# obc_imu.net
KiCad netlist of a schematic drawn in Altium Designer
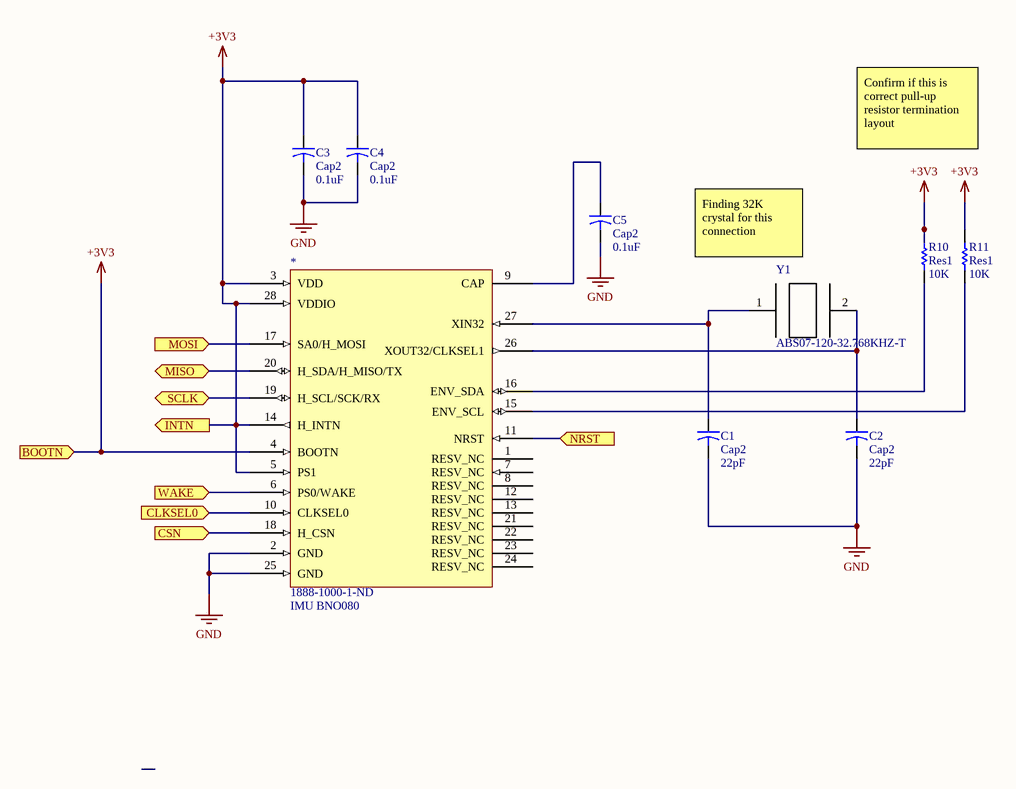
[diagram p0: obc_imu.SchDoc]

(export (version "E")
  (design (tool "Eeschema 10.0.6"))
  (components
    (comp (ref "*")
      (value "IMU BNO080")
      (description "ACCEL/GYRO/MAG I2C 32BIT")
      (libsource (lib "ICs") (part "IMU BNO080"))
    )
    (comp (ref "C1")
      (value "Cap2")
      (footprint "CAPR5-4X5")
      (description "Capacitor")
      (fields (field (name "ALTIUM_VALUE") "22pF") (field (name "PUBLISHER") "Altium Limited"))
      (libsource (lib "Miscellaneous Devices") (part "Cap2"))
    )
    (comp (ref "C2")
      (value "Cap2")
      (footprint "CAPR5-4X5")
      (description "Capacitor")
      (fields (field (name "ALTIUM_VALUE") "22pF") (field (name "PUBLISHER") "Altium Limited"))
      (libsource (lib "Miscellaneous Devices") (part "Cap2"))
    )
    (comp (ref "C3")
      (value "Cap2")
      (footprint "CAPR5-4X5")
      (description "Capacitor")
      (fields (field (name "ALTIUM_VALUE") "0.1uF") (field (name "PUBLISHER") "Altium Limited"))
      (libsource (lib "Miscellaneous Devices") (part "Cap2"))
    )
    (comp (ref "C4")
      (value "Cap2")
      (footprint "CAPR5-4X5")
      (description "Capacitor")
      (fields (field (name "ALTIUM_VALUE") "0.1uF") (field (name "PUBLISHER") "Altium Limited"))
      (libsource (lib "Miscellaneous Devices") (part "Cap2"))
    )
    (comp (ref "C5")
      (value "Cap2")
      (footprint "CAPR5-4X5")
      (description "Capacitor")
      (fields (field (name "ALTIUM_VALUE") "0.1uF") (field (name "PUBLISHER") "Altium Limited"))
      (libsource (lib "Miscellaneous Devices") (part "Cap2"))
    )
    (comp (ref "R10")
      (value "Res1")
      (footprint "AXIAL-0.3")
      (description "Resistor")
      (fields (field (name "ALTIUM_VALUE") "10K") (field (name "PUBLISHER") "Altium Limited"))
      (libsource (lib "Miscellaneous Devices") (part "Res1"))
    )
    (comp (ref "R11")
      (value "Res1")
      (footprint "AXIAL-0.3")
      (description "Resistor")
      (fields (field (name "ALTIUM_VALUE") "10K") (field (name "PUBLISHER") "Altium Limited"))
      (libsource (lib "Miscellaneous Devices") (part "Res1"))
    )
    (comp (ref "Y1")
      (value "ABS07-120-32.768KHZ-T")
      (footprint "XTAL_ABS07-120-32.768KHZ-T")
      (fields (field (name "MF") "Abracon"))
      (libsource (lib "ABS07-120-32.768KHZ-T") (part "ABS07-120-32.768KHZ-T"))
    )
  )
  (nets
    (net (code "1") (name "+3V3") (class "Default")
      (node (ref "*") (pin "14") (pinfunction "H_INTN_14") (pintype "output"))
      (node (ref "*") (pin "28") (pinfunction "VDDIO_28") (pintype "input"))
      (node (ref "*") (pin "3") (pinfunction "VDD_3") (pintype "input"))
      (node (ref "*") (pin "4") (pinfunction "BOOTN_4") (pintype "input"))
      (node (ref "*") (pin "5") (pinfunction "PS1_5") (pintype "input"))
      (node (ref "C3") (pin "1") (pinfunction "1_1") (pintype "passive"))
      (node (ref "C4") (pin "1") (pinfunction "1_1") (pintype "passive"))
      (node (ref "R10") (pin "2") (pinfunction "2_2") (pintype "passive"))
      (node (ref "R11") (pin "2") (pinfunction "2_2") (pintype "passive"))
    )
    (net (code "2") (name "/CLKSEL0") (class "Default")
      (node (ref "*") (pin "10") (pinfunction "CLKSEL0_10") (pintype "input"))
    )
    (net (code "3") (name "/CSN") (class "Default")
      (node (ref "*") (pin "18") (pinfunction "H_CSN_18") (pintype "input"))
    )
    (net (code "4") (name "/MISO") (class "Default")
      (node (ref "*") (pin "20") (pinfunction "H_SDA/H_MISO/TX_20") (pintype "bidirectional"))
    )
    (net (code "5") (name "/MOSI") (class "Default")
      (node (ref "*") (pin "17") (pinfunction "SA0/H_MOSI_17") (pintype "input"))
    )
    (net (code "6") (name "/NRST") (class "Default")
      (node (ref "*") (pin "11") (pinfunction "NRST_11") (pintype "input"))
    )
    (net (code "7") (name "/SCLK") (class "Default")
      (node (ref "*") (pin "19") (pinfunction "H_SCL/SCK/RX_19") (pintype "bidirectional"))
    )
    (net (code "8") (name "/WAKE") (class "Default")
      (node (ref "*") (pin "6") (pinfunction "PS0/WAKE_6") (pintype "input"))
    )
    (net (code "9") (name "GND") (class "Default")
      (node (ref "*") (pin "2") (pinfunction "GND_2") (pintype "input"))
      (node (ref "*") (pin "25") (pinfunction "GND_25") (pintype "input"))
      (node (ref "C1") (pin "2") (pinfunction "2_2") (pintype "passive"))
      (node (ref "C2") (pin "2") (pinfunction "2_2") (pintype "passive"))
      (node (ref "C3") (pin "2") (pinfunction "2_2") (pintype "passive"))
      (node (ref "C4") (pin "2") (pinfunction "2_2") (pintype "passive"))
      (node (ref "C5") (pin "2") (pinfunction "2_2") (pintype "passive"))
    )
    (net (code "10") (name "Net-(*-CAP)") (class "Default")
      (node (ref "*") (pin "9") (pinfunction "CAP_9") (pintype "passive"))
      (node (ref "C5") (pin "1") (pinfunction "1_1") (pintype "passive"))
    )
    (net (code "11") (name "Net-(*-ENV_SCL)") (class "Default")
      (node (ref "*") (pin "15") (pinfunction "ENV_SCL_15") (pintype "bidirectional"))
      (node (ref "R11") (pin "1") (pinfunction "1_1") (pintype "passive"))
    )
    (net (code "12") (name "Net-(*-ENV_SDA)") (class "Default")
      (node (ref "*") (pin "16") (pinfunction "ENV_SDA_16") (pintype "bidirectional"))
      (node (ref "R10") (pin "1") (pinfunction "1_1") (pintype "passive"))
    )
    (net (code "13") (name "Net-(*-XIN32)") (class "Default")
      (node (ref "*") (pin "27") (pinfunction "XIN32_27") (pintype "input"))
      (node (ref "C1") (pin "1") (pinfunction "1_1") (pintype "passive"))
      (node (ref "Y1") (pin "1") (pinfunction "1_1") (pintype "passive"))
    )
    (net (code "14") (name "Net-(*-XOUT32{slash}CLKSEL1)") (class "Default")
      (node (ref "*") (pin "26") (pinfunction "XOUT32/CLKSEL1_26") (pintype "output"))
      (node (ref "C2") (pin "1") (pinfunction "1_1") (pintype "passive"))
      (node (ref "Y1") (pin "2") (pinfunction "2_2") (pintype "passive"))
    )
    (net (code "15") (name "unconnected-(*-RESV_NC-Pad1)") (class "Default")
      (node (ref "*") (pin "1") (pinfunction "RESV_NC_1") (pintype "passive"))
    )
    (net (code "16") (name "unconnected-(*-RESV_NC-Pad7)") (class "Default")
      (node (ref "*") (pin "7") (pinfunction "RESV_NC_7") (pintype "input"))
    )
    (net (code "17") (name "unconnected-(*-RESV_NC-Pad8)") (class "Default")
      (node (ref "*") (pin "8") (pinfunction "RESV_NC_8") (pintype "passive"))
    )
    (net (code "18") (name "unconnected-(*-RESV_NC-Pad12)") (class "Default")
      (node (ref "*") (pin "12") (pinfunction "RESV_NC_12") (pintype "passive"))
    )
    (net (code "19") (name "unconnected-(*-RESV_NC-Pad13)") (class "Default")
      (node (ref "*") (pin "13") (pinfunction "RESV_NC_13") (pintype "passive"))
    )
    (net (code "20") (name "unconnected-(*-RESV_NC-Pad21)") (class "Default")
      (node (ref "*") (pin "21") (pinfunction "RESV_NC_21") (pintype "passive"))
    )
    (net (code "21") (name "unconnected-(*-RESV_NC-Pad22)") (class "Default")
      (node (ref "*") (pin "22") (pinfunction "RESV_NC_22") (pintype "passive"))
    )
    (net (code "22") (name "unconnected-(*-RESV_NC-Pad23)") (class "Default")
      (node (ref "*") (pin "23") (pinfunction "RESV_NC_23") (pintype "passive"))
    )
    (net (code "23") (name "unconnected-(*-RESV_NC-Pad24)") (class "Default")
      (node (ref "*") (pin "24") (pinfunction "RESV_NC_24") (pintype "passive"))
    )
  )
)
